# EEZ_PSU_AUX_PS_r5B9.net
KiCad netlist of a schematic drawn in EAGLE
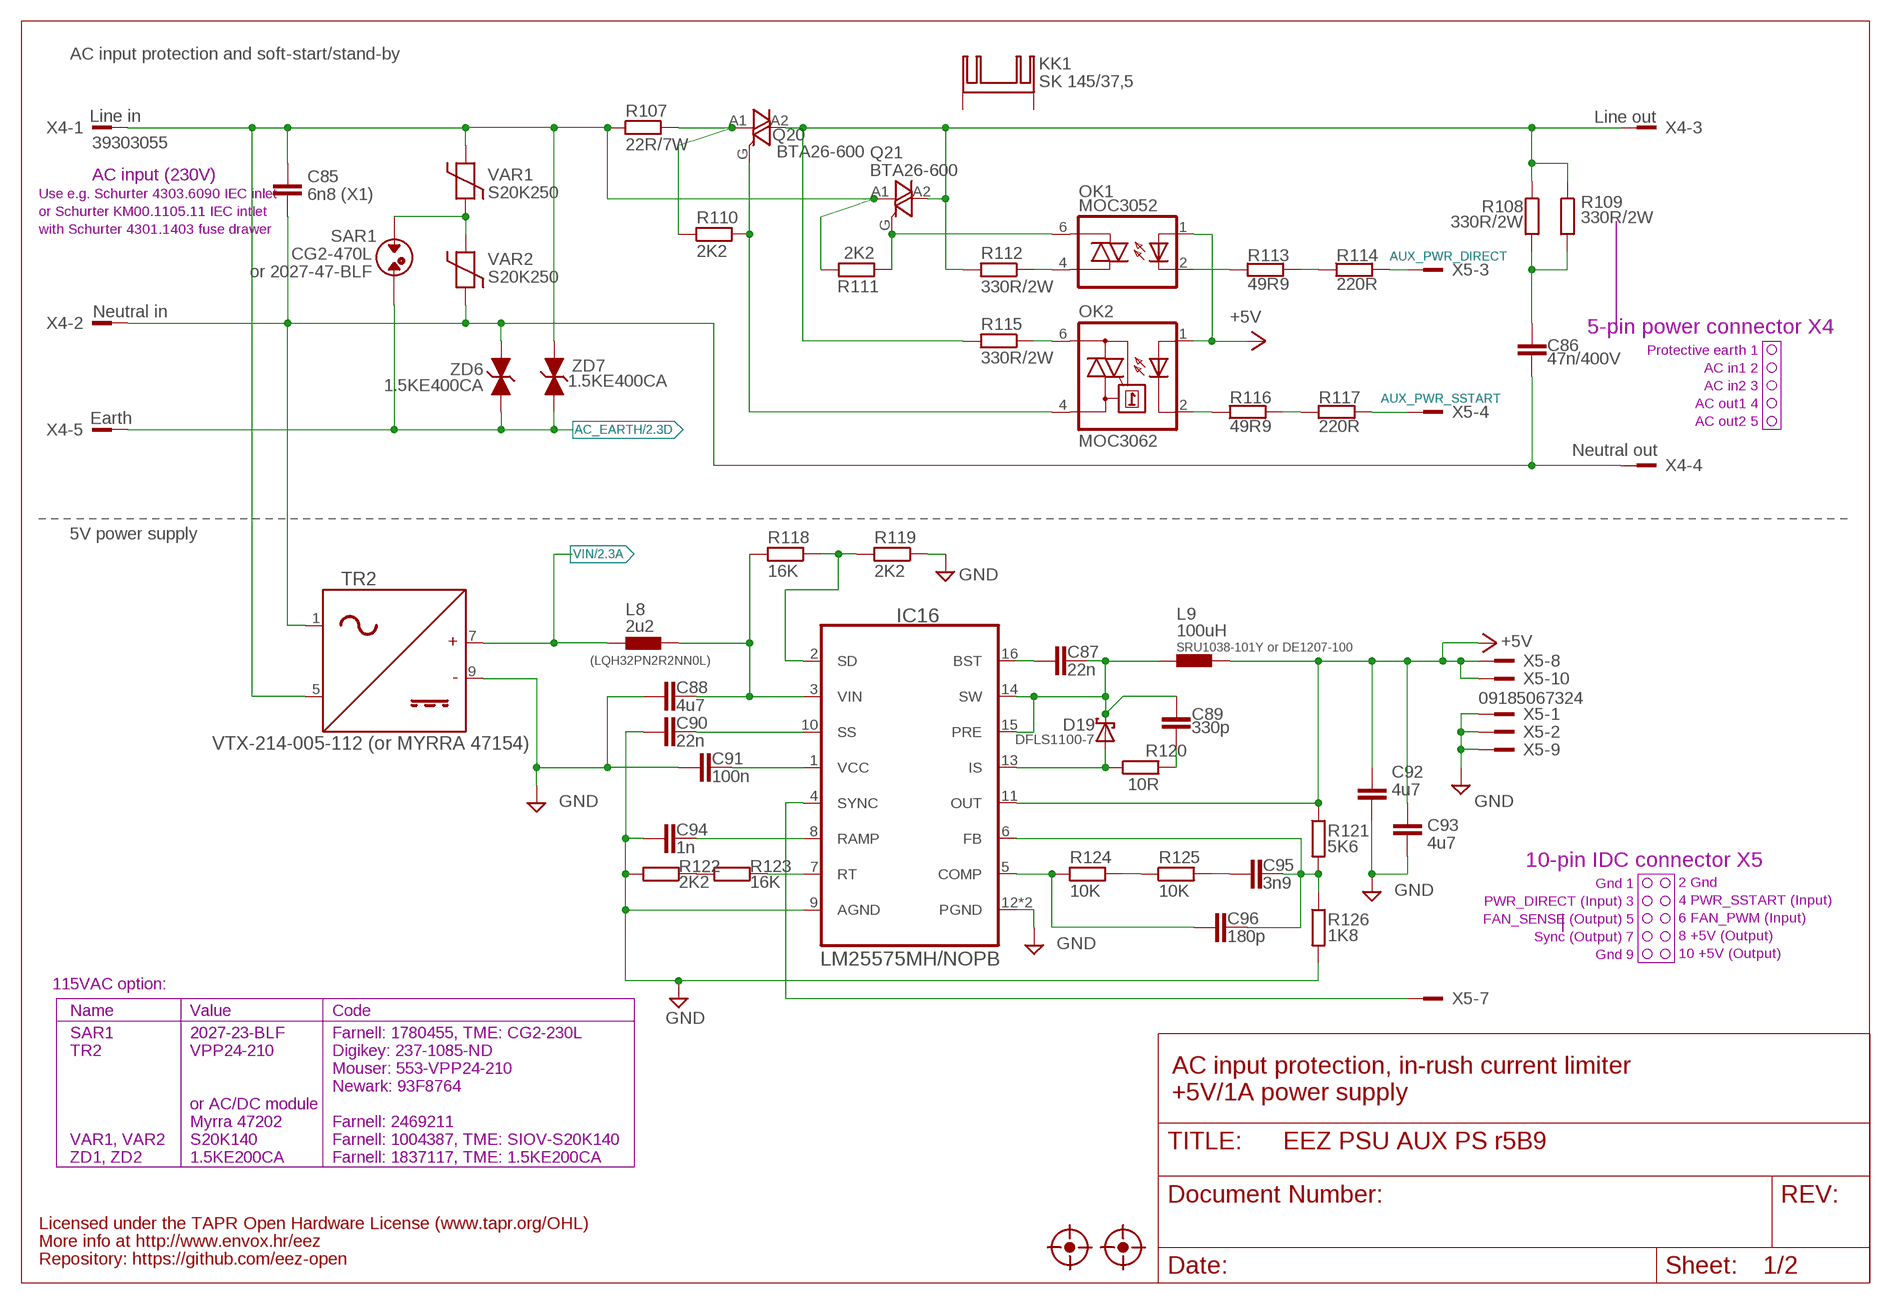
[diagram p0: schematic, sheet 1]
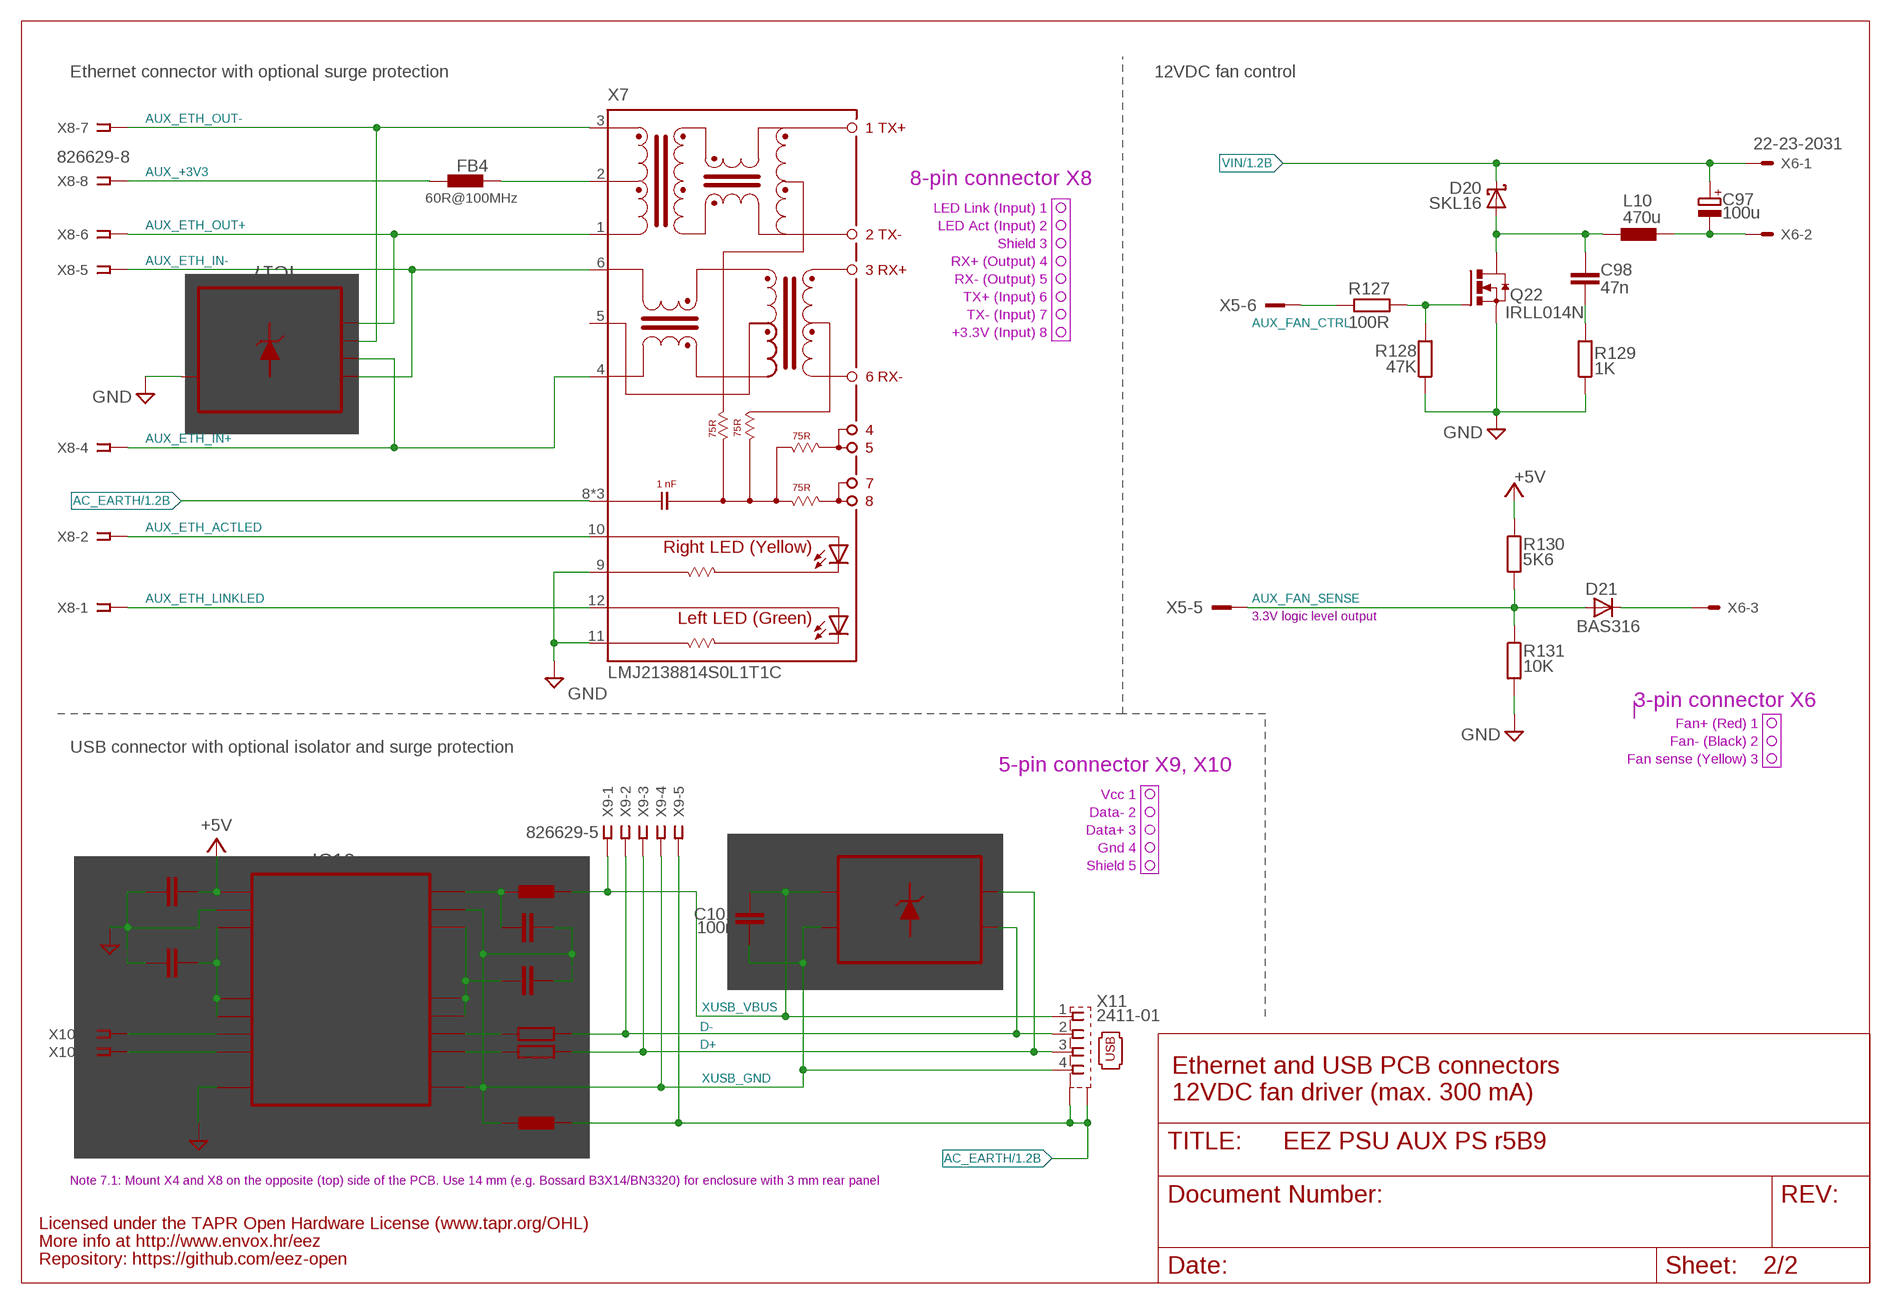
[diagram p1: schematic, sheet 2]

(export (version "E")
  (design (tool "Eeschema 10.0.6"))
  (components
    (comp (ref "C85")
      (value "6n8 (X1)")
      (footprint "eagle-import:C102-064X133")
      (libsource (lib "eagle-import") (part "C-EU102-064X133"))
    )
    (comp (ref "C86")
      (value "47n/400V")
      (footprint "eagle-import:C075-052X106")
      (libsource (lib "eagle-import") (part "C-EU075-052X106"))
    )
    (comp (ref "C87")
      (value "22n")
      (footprint "eagle-import:C0805")
      (libsource (lib "eagle-import") (part "C-EUC0805"))
    )
    (comp (ref "C88")
      (value "4u7")
      (footprint "eagle-import:C1210")
      (libsource (lib "eagle-import") (part "C-EUC1210"))
    )
    (comp (ref "C89")
      (value "330p")
      (footprint "eagle-import:C0805")
      (libsource (lib "eagle-import") (part "C-EUC0805"))
    )
    (comp (ref "C90")
      (value "22n")
      (footprint "eagle-import:C0805")
      (libsource (lib "eagle-import") (part "C-EUC0805"))
    )
    (comp (ref "C91")
      (value "100n")
      (footprint "eagle-import:C0603")
      (libsource (lib "eagle-import") (part "C-EUC0603"))
    )
    (comp (ref "C92")
      (value "4u7")
      (footprint "eagle-import:C1210")
      (libsource (lib "eagle-import") (part "C-EUC1210"))
    )
    (comp (ref "C93")
      (value "4u7")
      (footprint "eagle-import:C1210")
      (libsource (lib "eagle-import") (part "C-EUC1210"))
    )
    (comp (ref "C94")
      (value "1n")
      (footprint "eagle-import:C0805")
      (libsource (lib "eagle-import") (part "C-EUC0805"))
    )
    (comp (ref "C95")
      (value "3n9")
      (footprint "eagle-import:C0805")
      (libsource (lib "eagle-import") (part "C-EUC0805"))
    )
    (comp (ref "C96")
      (value "180p")
      (footprint "eagle-import:C0805")
      (libsource (lib "eagle-import") (part "C-EUC0805"))
    )
    (comp (ref "D19")
      (value "DFLS1100-7")
      (footprint "eagle-import:SOD123")
      (libsource (lib "eagle-import") (part "SCHOTTKYSOD123"))
    )
    (comp (ref "FM3")
      (value "FIDUCIAL_2")
      (footprint "eagle-import:FIDUCIAL_DUAL")
      (libsource (lib "eagle-import") (part "FIDUCIAL_2"))
    )
    (comp (ref "FM4")
      (value "FIDUCIAL_2")
      (footprint "eagle-import:FIDUCIAL_DUAL")
      (libsource (lib "eagle-import") (part "FIDUCIAL_2"))
    )
    (comp (ref "IC16")
      (value "LM25575MH/NOPB")
      (footprint "eagle-import:SOP65P640X110-17N")
      (libsource (lib "eagle-import") (part "LM(2)5575"))
    )
    (comp (ref "KK1")
      (value "SK 145/37,5")
      (footprint "eagle-import:SK145")
      (libsource (lib "eagle-import") (part "SK145"))
    )
    (comp (ref "L8")
      (value "2u2")
      (footprint "eagle-import:L1210")
      (libsource (lib "eagle-import") (part "L1210"))
    )
    (comp (ref "L9")
      (value "100uH")
      (footprint "eagle-import:MSS1278")
      (libsource (lib "eagle-import") (part "COILCRAFT_MSS1278"))
    )
    (comp (ref "OK1")
      (value "MOC3052")
      (footprint "eagle-import:DIL6-SMD")
      (libsource (lib "eagle-import") (part "MOC305X"))
    )
    (comp (ref "OK2")
      (value "MOC3062")
      (footprint "eagle-import:DIL6-SMD")
      (fields
        (field (name "MF") "FAIRCHILD SEMICONDUCTOR")
        (field (name "MPN") "MOC3033S-M")
        (field (name "MF_1") "FAIRCHILD SEMICONDUCTOR")
        (field (name "MPN_1") "MOC3033S-M")
        (field (name "OC_FARNELL") "unknown")
        (field (name "OC_NEWARK") "05C2878")
      )
      (libsource (lib "eagle-import") (part "MOC30S33"))
    )
    (comp (ref "Q20")
      (value "BTA26-600")
      (footprint "eagle-import:TOP3S-1")
      (libsource (lib "eagle-import") (part "BTA26-V"))
    )
    (comp (ref "Q21")
      (value "BTA26-600")
      (footprint "eagle-import:TOP3S-1")
      (libsource (lib "eagle-import") (part "BTA26-V"))
    )
    (comp (ref "R107")
      (value "22R/7W")
      (footprint "eagle-import:R_0913")
      (libsource (lib "eagle-import") (part "R_EU7W"))
    )
    (comp (ref "R108")
      (value "330R/2W")
      (footprint "eagle-import:R2512")
      (libsource (lib "eagle-import") (part "R-EU_R2512"))
    )
    (comp (ref "R109")
      (value "330R/2W")
      (footprint "eagle-import:R2512")
      (libsource (lib "eagle-import") (part "R-EU_R2512"))
    )
    (comp (ref "R110")
      (value "2K2")
      (footprint "eagle-import:R0805")
      (libsource (lib "eagle-import") (part "R-EU_R0805"))
    )
    (comp (ref "R111")
      (value "2K2")
      (footprint "eagle-import:R0805")
      (libsource (lib "eagle-import") (part "R-EU_R0805"))
    )
    (comp (ref "R112")
      (value "330R/2W")
      (footprint "eagle-import:R2512")
      (libsource (lib "eagle-import") (part "R-EU_R2512"))
    )
    (comp (ref "R113")
      (value "49R9")
      (footprint "eagle-import:R0805")
      (libsource (lib "eagle-import") (part "R-EU_R0805"))
    )
    (comp (ref "R114")
      (value "220R")
      (footprint "eagle-import:R0805")
      (libsource (lib "eagle-import") (part "R-EU_R0805"))
    )
    (comp (ref "R115")
      (value "330R/2W")
      (footprint "eagle-import:R2512")
      (libsource (lib "eagle-import") (part "R-EU_R2512"))
    )
    (comp (ref "R116")
      (value "49R9")
      (footprint "eagle-import:R0805")
      (libsource (lib "eagle-import") (part "R-EU_R0805"))
    )
    (comp (ref "R117")
      (value "220R")
      (footprint "eagle-import:R0805")
      (libsource (lib "eagle-import") (part "R-EU_R0805"))
    )
    (comp (ref "R118")
      (value "16K")
      (footprint "eagle-import:R0805")
      (libsource (lib "eagle-import") (part "R-EU_R0805"))
    )
    (comp (ref "R119")
      (value "2K2")
      (footprint "eagle-import:R0805")
      (libsource (lib "eagle-import") (part "R-EU_R0805"))
    )
    (comp (ref "R120")
      (value "10R")
      (footprint "eagle-import:R1206")
      (libsource (lib "eagle-import") (part "R-EU_R1206"))
    )
    (comp (ref "R121")
      (value "5K6")
      (footprint "eagle-import:R0805")
      (libsource (lib "eagle-import") (part "R-EU_R0805"))
    )
    (comp (ref "R122")
      (value "2K2")
      (footprint "eagle-import:R0805")
      (libsource (lib "eagle-import") (part "R-EU_R0805"))
    )
    (comp (ref "R123")
      (value "16K")
      (footprint "eagle-import:R0805")
      (libsource (lib "eagle-import") (part "R-EU_R0805"))
    )
    (comp (ref "R124")
      (value "10K")
      (footprint "eagle-import:R0805")
      (libsource (lib "eagle-import") (part "R-EU_R0805"))
    )
    (comp (ref "R125")
      (value "10K")
      (footprint "eagle-import:R0805")
      (libsource (lib "eagle-import") (part "R-EU_R0805"))
    )
    (comp (ref "R126")
      (value "1K8")
      (footprint "eagle-import:R0805")
      (libsource (lib "eagle-import") (part "R-EU_R0805"))
    )
    (comp (ref "SAR1")
      (value "CG2-470L")
      (footprint "eagle-import:SAR")
      (libsource (lib "eagle-import") (part "SAR"))
    )
    (comp (ref "TR2")
      (value "VTX-214-005-112 (or MYRRA 47154)")
      (footprint "eagle-import:PCB_ACDC_MYRRA_5W")
      (libsource (lib "eagle-import") (part "AC_DC_ADAPTER_5W"))
    )
    (comp (ref "VAR1")
      (value "S20K250")
      (footprint "eagle-import:VARISTOR")
      (libsource (lib "eagle-import") (part "VARISTOR"))
    )
    (comp (ref "VAR2")
      (value "S20K250")
      (footprint "eagle-import:VARISTOR")
      (libsource (lib "eagle-import") (part "VARISTOR"))
    )
    (comp (ref "X4")
      (value "39303055")
      (footprint "eagle-import:MINIFIT_6659-5")
      (libsource (lib "eagle-import") (part "MINIFIT_6659-5"))
    )
    (comp (ref "X5")
      (value "09185067324")
      (footprint "eagle-import:IDC-10PIN")
      (fields (field (name "TME") "T821-1-10-S1 "))
      (libsource (lib "eagle-import") (part "IDC-10PINBLACK"))
    )
    (comp (ref "ZD6")
      (value "1.5KE400CA")
      (footprint "eagle-import:DO201-BIDIR")
      (libsource (lib "eagle-import") (part "1.5KE-BIDIR"))
    )
    (comp (ref "ZD7")
      (value "1.5KE400CA")
      (footprint "eagle-import:DO201-BIDIR")
      (libsource (lib "eagle-import") (part "1.5KE-BIDIR"))
    )
    (comp (ref "C97")
      (value "100u")
      (footprint "eagle-import:CAPAE660X610N")
      (libsource (lib "eagle-import") (part "ECAPPANASONIC_H"))
    )
    (comp (ref "C98")
      (value "47n")
      (footprint "eagle-import:C0805")
      (libsource (lib "eagle-import") (part "C-EUC0805"))
    )
    (comp (ref "C99")
      (value "100n")
      (footprint "eagle-import:C0603")
      (libsource (lib "eagle-import") (part "C-EUC0603"))
    )
    (comp (ref "C100")
      (value "100n")
      (footprint "eagle-import:C0603")
      (libsource (lib "eagle-import") (part "C-EUC0603"))
    )
    (comp (ref "C101")
      (value "100n")
      (footprint "eagle-import:C0603")
      (libsource (lib "eagle-import") (part "C-EUC0603"))
    )
    (comp (ref "C102")
      (value "100n")
      (footprint "eagle-import:C0603")
      (libsource (lib "eagle-import") (part "C-EUC0603"))
    )
    (comp (ref "C103")
      (value "100n")
      (footprint "eagle-import:C0603")
      (libsource (lib "eagle-import") (part "C-EUC0603"))
    )
    (comp (ref "D20")
      (value "SKL16")
      (footprint "eagle-import:SOD123")
      (libsource (lib "eagle-import") (part "SCHOTTKYSOD123"))
    )
    (comp (ref "D21")
      (value "BAS316")
      (footprint "eagle-import:SOD323-W")
      (libsource (lib "eagle-import") (part "DIODE-SOD323-W"))
    )
    (comp (ref "FB4")
      (value "60R@100MHz")
      (footprint "eagle-import:BEAD0603")
      (libsource (lib "eagle-import") (part "FERRITE_BEAD0603"))
    )
    (comp (ref "FB5")
      (value "60R@100MHz")
      (footprint "eagle-import:BEAD0603")
      (libsource (lib "eagle-import") (part "FERRITE_BEAD0603"))
    )
    (comp (ref "FB6")
      (value "60R@100MHz")
      (footprint "eagle-import:BEAD0603")
      (libsource (lib "eagle-import") (part "FERRITE_BEAD0603"))
    )
    (comp (ref "IC17")
      (value "TPD4E002DRLR")
      (footprint "eagle-import:SOT50P280X60-5N")
      (libsource (lib "eagle-import") (part "TPD4E002DRLR"))
    )
    (comp (ref "IC18")
      (value "TPD2E001DZDR")
      (footprint "eagle-import:SOP192P292X122-4N")
      (libsource (lib "eagle-import") (part "TPD2E001DZDR"))
    )
    (comp (ref "IC19")
      (value "ADUM3160BRWZ")
      (footprint "eagle-import:SOIC-16W")
      (libsource (lib "eagle-import") (part "ADUM3160BRWZWIDE"))
    )
    (comp (ref "L10")
      (value "470u")
      (footprint "eagle-import:DE0704")
      (libsource (lib "eagle-import") (part "DE0704"))
    )
    (comp (ref "Q22")
      (value "IRLL014N")
      (footprint "eagle-import:SOT223")
      (libsource (lib "eagle-import") (part "N-HEXFET-2D_?-SOT232IRLL014N"))
    )
    (comp (ref "R127")
      (value "100R")
      (footprint "eagle-import:R0805")
      (libsource (lib "eagle-import") (part "R-EU_R0805"))
    )
    (comp (ref "R128")
      (value "47K")
      (footprint "eagle-import:R0805")
      (libsource (lib "eagle-import") (part "R-EU_R0805"))
    )
    (comp (ref "R129")
      (value "1K")
      (footprint "eagle-import:R0805")
      (libsource (lib "eagle-import") (part "R-EU_R0805"))
    )
    (comp (ref "R130")
      (value "5K6")
      (footprint "eagle-import:R0805")
      (libsource (lib "eagle-import") (part "R-EU_R0805"))
    )
    (comp (ref "R131")
      (value "10K")
      (footprint "eagle-import:R0805")
      (libsource (lib "eagle-import") (part "R-EU_R0805"))
    )
    (comp (ref "R132")
      (value "22R")
      (footprint "eagle-import:R0805")
      (libsource (lib "eagle-import") (part "R-EU_R0805"))
    )
    (comp (ref "R133")
      (value "22R")
      (footprint "eagle-import:R0805")
      (libsource (lib "eagle-import") (part "R-EU_R0805"))
    )
    (comp (ref "X6")
      (value "22-23-2031")
      (footprint "eagle-import:22-23-2031")
      (fields (field (name "MF") "MOLEX"))
      (libsource (lib "eagle-import") (part "22-23-2031"))
    )
    (comp (ref "X7")
      (value "LMJ2138814S0L1T1C")
      (footprint "eagle-import:RJ45-VERT")
      (libsource (lib "eagle-import") (part "RJ45-VERTLMJ2138814S0L1T1C"))
    )
    (comp (ref "X8")
      (value "826629-8")
      (footprint "eagle-import:SSW-108-02-S-S")
      (fields (field (name "MPN") "SSW-108-02-S-S"))
      (libsource (lib "eagle-import") (part "SSW-108-02-S-S"))
    )
    (comp (ref "X9")
      (value "826629-5")
      (footprint "eagle-import:SSW-105-02-S-S")
      (fields (field (name "MPN") "SSW-105-02-S-S"))
      (libsource (lib "eagle-import") (part "SSW-105-02-S-S"))
    )
    (comp (ref "X10")
      (value "826629-5")
      (footprint "eagle-import:SSW-105-02-S-S")
      (fields (field (name "MPN") "SSW-105-02-S-S"))
      (libsource (lib "eagle-import") (part "SSW-105-02-S-S"))
    )
    (comp (ref "X11")
      (value "2411-01")
      (footprint "eagle-import:KUSBVX-BS1N")
      (libsource (lib "eagle-import") (part "KUSBVX-BS1N"))
    )
  )
  (nets
    (net (code "1") (name "+5V") (class "Default")
      (node (ref "C92") (pin "1") (pinfunction "1_1") (pintype "passive"))
      (node (ref "C93") (pin "1") (pinfunction "1_1") (pintype "passive"))
      (node (ref "C99") (pin "1") (pinfunction "1_1") (pintype "passive"))
      (node (ref "IC16") (pin "11") (pinfunction "OUT_11") (pintype "output"))
      (node (ref "IC19") (pin "16") (pinfunction "VBUS2_16") (pintype "power_in"))
      (node (ref "L9") (pin "2") (pinfunction "2_2") (pintype "passive"))
      (node (ref "OK1") (pin "1") (pinfunction "A_1") (pintype "passive"))
      (node (ref "OK2") (pin "1") (pinfunction "A_1") (pintype "passive"))
      (node (ref "R121") (pin "1") (pinfunction "1_1") (pintype "passive"))
      (node (ref "R130") (pin "1") (pinfunction "1_1") (pintype "passive"))
      (node (ref "X5") (pin "10") (pinfunction "1_10") (pintype "passive"))
      (node (ref "X5") (pin "8") (pinfunction "1_8") (pintype "passive"))
    )
    (net (code "2") (name "AC_EARTH") (class "Default")
      (node (ref "FB6") (pin "P$1") (pinfunction "1_P$1") (pintype "passive"))
      (node (ref "SAR1") (pin "P$2") (pinfunction "P$2_P$2") (pintype "bidirectional"))
      (node (ref "X11") (pin "M1") (pinfunction "S1_M1") (pintype "passive"))
      (node (ref "X11") (pin "M2") (pinfunction "S2_M2") (pintype "passive"))
      (node (ref "X4") (pin "5") (pinfunction "1_5") (pintype "passive"))
      (node (ref "X7") (pin "8") (pinfunction "SH_8") (pintype "input"))
      (node (ref "X7") (pin "SH1") (pinfunction "SH_SH1") (pintype "input"))
      (node (ref "X7") (pin "SH2") (pinfunction "SH_SH2") (pintype "input"))
      (node (ref "X9") (pin "5") (pinfunction "1_5") (pintype "passive"))
      (node (ref "ZD6") (pin "C") (pinfunction "1_C") (pintype "passive"))
      (node (ref "ZD7") (pin "C") (pinfunction "1_C") (pintype "passive"))
    )
    (net (code "3") (name "AUX_+3V3") (class "Default")
      (node (ref "FB4") (pin "P$2") (pinfunction "2_P$2") (pintype "passive"))
      (node (ref "X8") (pin "8") (pinfunction "1_8") (pintype "passive"))
    )
    (net (code "4") (name "AUX_ETH_ACTLED") (class "Default")
      (node (ref "X7") (pin "10") (pinfunction "YELLOW_A_10") (pintype "passive"))
      (node (ref "X8") (pin "2") (pinfunction "1_2") (pintype "passive"))
    )
    (net (code "5") (name "AUX_ETH_IN+") (class "Default")
      (node (ref "IC17") (pin "4") (pinfunction "IO3_4") (pintype "bidirectional"))
      (node (ref "X7") (pin "4") (pinfunction "RD-_4") (pintype "input"))
      (node (ref "X8") (pin "4") (pinfunction "1_4") (pintype "passive"))
    )
    (net (code "6") (name "AUX_ETH_IN-") (class "Default")
      (node (ref "IC17") (pin "5") (pinfunction "IO4_5") (pintype "bidirectional"))
      (node (ref "X7") (pin "6") (pinfunction "RD+_6") (pintype "input"))
      (node (ref "X8") (pin "5") (pinfunction "1_5") (pintype "passive"))
    )
    (net (code "7") (name "AUX_ETH_LINKLED") (class "Default")
      (node (ref "X7") (pin "12") (pinfunction "GREEN-A_12") (pintype "passive"))
      (node (ref "X8") (pin "1") (pinfunction "1_1") (pintype "passive"))
    )
    (net (code "8") (name "AUX_ETH_OUT+") (class "Default")
      (node (ref "IC17") (pin "1") (pinfunction "IO1_1") (pintype "bidirectional"))
      (node (ref "X7") (pin "1") (pinfunction "TD-_1") (pintype "input"))
      (node (ref "X8") (pin "6") (pinfunction "1_6") (pintype "passive"))
    )
    (net (code "9") (name "AUX_ETH_OUT-") (class "Default")
      (node (ref "IC17") (pin "3") (pinfunction "IO2_3") (pintype "bidirectional"))
      (node (ref "X7") (pin "3") (pinfunction "TD+_3") (pintype "input"))
      (node (ref "X8") (pin "7") (pinfunction "1_7") (pintype "passive"))
    )
    (net (code "10") (name "AUX_FAN_CTRL") (class "Default")
      (node (ref "R127") (pin "2") (pinfunction "2_2") (pintype "passive"))
      (node (ref "X5") (pin "6") (pinfunction "1_6") (pintype "passive"))
    )
    (net (code "11") (name "AUX_FAN_SENSE") (class "Default")
      (node (ref "D21") (pin "A") (pinfunction "A_A") (pintype "passive"))
      (node (ref "R130") (pin "2") (pinfunction "2_2") (pintype "passive"))
      (node (ref "R131") (pin "1") (pinfunction "1_1") (pintype "passive"))
      (node (ref "X5") (pin "5") (pinfunction "1_5") (pintype "passive"))
    )
    (net (code "12") (name "AUX_PWR_DIRECT") (class "Default")
      (node (ref "R114") (pin "2") (pinfunction "2_2") (pintype "passive"))
      (node (ref "X5") (pin "3") (pinfunction "1_3") (pintype "passive"))
    )
    (net (code "13") (name "AUX_PWR_SSTART") (class "Default")
      (node (ref "R117") (pin "2") (pinfunction "2_2") (pintype "passive"))
      (node (ref "X5") (pin "4") (pinfunction "1_4") (pintype "passive"))
    )
    (net (code "14") (name "D+") (class "Default")
      (node (ref "IC18") (pin "2") (pinfunction "IO1_2") (pintype "bidirectional"))
      (node (ref "R133") (pin "1") (pinfunction "1_1") (pintype "passive"))
      (node (ref "X11") (pin "3") (pinfunction "3_3") (pintype "passive"))
      (node (ref "X9") (pin "3") (pinfunction "1_3") (pintype "passive"))
    )
    (net (code "15") (name "D-") (class "Default")
      (node (ref "IC18") (pin "3") (pinfunction "IO2_3") (pintype "bidirectional"))
      (node (ref "R132") (pin "1") (pinfunction "1_1") (pintype "passive"))
      (node (ref "X11") (pin "2") (pinfunction "2_2") (pintype "passive"))
      (node (ref "X9") (pin "2") (pinfunction "1_2") (pintype "passive"))
    )
    (net (code "16") (name "GND") (class "Default")
      (node (ref "C102") (pin "2") (pinfunction "2_2") (pintype "passive"))
      (node (ref "C88") (pin "2") (pinfunction "2_2") (pintype "passive"))
      (node (ref "C90") (pin "2") (pinfunction "2_2") (pintype "passive"))
      (node (ref "C91") (pin "1") (pinfunction "1_1") (pintype "passive"))
      (node (ref "C92") (pin "2") (pinfunction "2_2") (pintype "passive"))
      (node (ref "C93") (pin "2") (pinfunction "2_2") (pintype "passive"))
      (node (ref "C94") (pin "1") (pinfunction "1_1") (pintype "passive"))
      (node (ref "C99") (pin "2") (pinfunction "2_2") (pintype "passive"))
      (node (ref "IC16") (pin "12") (pinfunction "PGND_12") (pintype "passive"))
      (node (ref "IC16") (pin "9") (pinfunction "AGND_9") (pintype "passive"))
      (node (ref "IC16") (pin "TP") (pinfunction "PGND_TP") (pintype "passive"))
      (node (ref "IC17") (pin "2") (pinfunction "GND_2") (pintype "passive"))
      (node (ref "IC19") (pin "15") (pinfunction "GND2_2_15") (pintype "passive"))
      (node (ref "IC19") (pin "9") (pinfunction "GND2_9") (pintype "passive"))
      (node (ref "Q22") (pin "3") (pinfunction "S_3") (pintype "passive"))
      (node (ref "R119") (pin "1") (pinfunction "1_1") (pintype "passive"))
      (node (ref "R122") (pin "2") (pinfunction "2_2") (pintype "passive"))
      (node (ref "R126") (pin "2") (pinfunction "2_2") (pintype "passive"))
      (node (ref "R128") (pin "1") (pinfunction "1_1") (pintype "passive"))
      (node (ref "R129") (pin "1") (pinfunction "1_1") (pintype "passive"))
      (node (ref "R131") (pin "2") (pinfunction "2_2") (pintype "passive"))
      (node (ref "TR2") (pin "9") (pinfunction "-_9") (pintype "passive"))
      (node (ref "X5") (pin "1") (pinfunction "1_1") (pintype "passive"))
      (node (ref "X5") (pin "2") (pinfunction "1_2") (pintype "passive"))
      (node (ref "X5") (pin "9") (pinfunction "1_9") (pintype "passive"))
      (node (ref "X7") (pin "11") (pinfunction "GREEN-C_11") (pintype "passive"))
      (node (ref "X7") (pin "9") (pinfunction "YELLOW-C_9") (pintype "passive"))
    )
    (net (code "17") (name "Net-(C86-Pad2)") (class "Default")
      (node (ref "C86") (pin "2") (pinfunction "2_2") (pintype "passive"))
      (node (ref "R108") (pin "2") (pinfunction "2_2") (pintype "passive"))
      (node (ref "R109") (pin "2") (pinfunction "2_2") (pintype "passive"))
    )
    (net (code "18") (name "Net-(C89-Pad2)") (class "Default")
      (node (ref "C89") (pin "2") (pinfunction "2_2") (pintype "passive"))
      (node (ref "R120") (pin "2") (pinfunction "2_2") (pintype "passive"))
    )
    (net (code "19") (name "Net-(C95-Pad2)") (class "Default")
      (node (ref "C95") (pin "2") (pinfunction "2_2") (pintype "passive"))
      (node (ref "R125") (pin "2") (pinfunction "2_2") (pintype "passive"))
    )
    (net (code "20") (name "Net-(C97--)") (class "Default")
      (node (ref "C97") (pin "2") (pinfunction "-_2") (pintype "passive"))
      (node (ref "L10") (pin "1") (pinfunction "1_1") (pintype "passive"))
      (node (ref "X6") (pin "2") (pinfunction "S_2") (pintype "passive"))
    )
    (net (code "21") (name "Net-(C98-Pad1)") (class "Default")
      (node (ref "C98") (pin "1") (pinfunction "1_1") (pintype "passive"))
      (node (ref "R129") (pin "2") (pinfunction "2_2") (pintype "passive"))
    )
    (net (code "22") (name "Net-(C98-Pad2)") (class "Default")
      (node (ref "C98") (pin "2") (pinfunction "2_2") (pintype "passive"))
      (node (ref "D20") (pin "A") (pinfunction "A_A") (pintype "passive"))
      (node (ref "L10") (pin "2") (pinfunction "2_2") (pintype "passive"))
      (node (ref "Q22") (pin "2") (pinfunction "D_2") (pintype "passive"))
      (node (ref "Q22") (pin "4") (pinfunction "D_4") (pintype "passive"))
    )
    (net (code "23") (name "Net-(FB4-1)") (class "Default")
      (node (ref "FB4") (pin "P$1") (pinfunction "1_P$1") (pintype "passive"))
      (node (ref "X7") (pin "2") (pinfunction "CT_2") (pintype "input"))
    )
    (net (code "24") (name "Net-(FB5-2)") (class "Default")
      (node (ref "C100") (pin "1") (pinfunction "1_1") (pintype "passive"))
      (node (ref "FB5") (pin "P$2") (pinfunction "2_P$2") (pintype "passive"))
      (node (ref "IC19") (pin "1") (pinfunction "VBUS1_1") (pintype "power_in"))
    )
    (net (code "25") (name "Net-(IC16-BST)") (class "Default")
      (node (ref "C87") (pin "2") (pinfunction "2_2") (pintype "passive"))
      (node (ref "IC16") (pin "16") (pinfunction "BST_16") (pintype "input"))
    )
    (net (code "26") (name "Net-(IC16-COMP)") (class "Default")
      (node (ref "C96") (pin "2") (pinfunction "2_2") (pintype "passive"))
      (node (ref "IC16") (pin "5") (pinfunction "COMP_5") (pintype "input"))
      (node (ref "R124") (pin "1") (pinfunction "1_1") (pintype "passive"))
    )
    (net (code "27") (name "Net-(IC16-FB)") (class "Default")
      (node (ref "C95") (pin "1") (pinfunction "1_1") (pintype "passive"))
      (node (ref "C96") (pin "1") (pinfunction "1_1") (pintype "passive"))
      (node (ref "IC16") (pin "6") (pinfunction "FB_6") (pintype "input"))
      (node (ref "R121") (pin "2") (pinfunction "2_2") (pintype "passive"))
      (node (ref "R126") (pin "1") (pinfunction "1_1") (pintype "passive"))
    )
    (net (code "28") (name "Net-(IC16-IS)") (class "Default")
      (node (ref "D19") (pin "A") (pinfunction "A_A") (pintype "passive"))
      (node (ref "IC16") (pin "13") (pinfunction "IS_13") (pintype "input"))
      (node (ref "R120") (pin "1") (pinfunction "1_1") (pintype "passive"))
    )
    (net (code "29") (name "Net-(IC16-PRE)") (class "Default")
      (node (ref "C87") (pin "1") (pinfunction "1_1") (pintype "passive"))
      (node (ref "C89") (pin "1") (pinfunction "1_1") (pintype "passive"))
      (node (ref "D19") (pin "C") (pinfunction "C_C") (pintype "passive"))
      (node (ref "IC16") (pin "14") (pinfunction "SW_14") (pintype "output"))
      (node (ref "IC16") (pin "15") (pinfunction "PRE_15") (pintype "input"))
      (node (ref "L9") (pin "1") (pinfunction "1_1") (pintype "passive"))
    )
    (net (code "30") (name "Net-(IC16-RAMP)") (class "Default")
      (node (ref "C94") (pin "2") (pinfunction "2_2") (pintype "passive"))
      (node (ref "IC16") (pin "8") (pinfunction "RAMP_8") (pintype "input"))
    )
    (net (code "31") (name "Net-(IC16-RT)") (class "Default")
      (node (ref "IC16") (pin "7") (pinfunction "RT_7") (pintype "input"))
      (node (ref "R123") (pin "1") (pinfunction "1_1") (pintype "passive"))
    )
    (net (code "32") (name "Net-(IC16-SD)") (class "Default")
      (node (ref "IC16") (pin "2") (pinfunction "SD_2") (pintype "input"))
      (node (ref "R118") (pin "1") (pinfunction "1_1") (pintype "passive"))
      (node (ref "R119") (pin "2") (pinfunction "2_2") (pintype "passive"))
    )
    (net (code "33") (name "Net-(IC16-SS)") (class "Default")
      (node (ref "C90") (pin "1") (pinfunction "1_1") (pintype "passive"))
      (node (ref "IC16") (pin "10") (pinfunction "SS_10") (pintype "input"))
    )
    (net (code "34") (name "Net-(IC16-SYNC)") (class "Default")
      (node (ref "IC16") (pin "4") (pinfunction "SYNC_4") (pintype "input"))
      (node (ref "X5") (pin "7") (pinfunction "1_7") (pintype "passive"))
    )
    (net (code "35") (name "Net-(IC16-VCC)") (class "Default")
      (node (ref "C91") (pin "2") (pinfunction "2_2") (pintype "passive"))
      (node (ref "IC16") (pin "1") (pinfunction "VCC_1") (pintype "power_in"))
    )
    (net (code "36") (name "Net-(IC16-VIN)") (class "Default")
      (node (ref "C88") (pin "1") (pinfunction "1_1") (pintype "passive"))
      (node (ref "IC16") (pin "3") (pinfunction "VIN_3") (pintype "input"))
      (node (ref "L8") (pin "2") (pinfunction "2_2") (pintype "passive"))
      (node (ref "R118") (pin "2") (pinfunction "2_2") (pintype "passive"))
    )
    (net (code "37") (name "Net-(IC19-DD+)") (class "Default")
      (node (ref "IC19") (pin "10") (pinfunction "DD+_10") (pintype "bidirectional"))
      (node (ref "X10") (pin "3") (pinfunction "1_3") (pintype "passive"))
    )
    (net (code "38") (name "Net-(IC19-DD-)") (class "Default")
      (node (ref "IC19") (pin "11") (pinfunction "DD-_11") (pintype "bidirectional"))
      (node (ref "X10") (pin "2") (pinfunction "1_2") (pintype "passive"))
    )
    (net (code "39") (name "Net-(IC19-PDEN)") (class "Default")
      (node (ref "C103") (pin "1") (pinfunction "1_1") (pintype "passive"))
      (node (ref "IC19") (pin "3") (pinfunction "VDD1_3") (pintype "power_in"))
      (node (ref "IC19") (pin "4") (pinfunction "PDEN_4") (pintype "input"))
      (node (ref "IC19") (pin "5") (pinfunction "SPU_5") (pintype "input"))
    )
    (net (code "40") (name "Net-(IC19-PIN)") (class "Default")
      (node (ref "C102") (pin "1") (pinfunction "1_1") (pintype "passive"))
      (node (ref "IC19") (pin "12") (pinfunction "PIN_12") (pintype "input"))
      (node (ref "IC19") (pin "13") (pinfunction "SPD_13") (pintype "input"))
      (node (ref "IC19") (pin "14") (pinfunction "VDD2_14") (pintype "power_in"))
    )
    (net (code "41") (name "Net-(IC19-UD+)") (class "Default")
      (node (ref "IC19") (pin "7") (pinfunction "UD+_7") (pintype "bidirectional"))
      (node (ref "R133") (pin "2") (pinfunction "2_2") (pintype "passive"))
    )
    (net (code "42") (name "Net-(IC19-UD-)") (class "Default")
      (node (ref "IC19") (pin "6") (pinfunction "UD-_6") (pintype "bidirectional"))
      (node (ref "R132") (pin "2") (pinfunction "2_2") (pintype "passive"))
    )
    (net (code "43") (name "Net-(OK1-A1)") (class "Default")
      (node (ref "OK1") (pin "4") (pinfunction "A1_4") (pintype "passive"))
      (node (ref "R112") (pin "1") (pinfunction "1_1") (pintype "passive"))
    )
    (net (code "44") (name "Net-(OK1-A2)") (class "Default")
      (node (ref "OK1") (pin "6") (pinfunction "A2_6") (pintype "passive"))
      (node (ref "Q21") (pin "G") (pinfunction "G_G") (pintype "passive"))
      (node (ref "R111") (pin "1") (pinfunction "1_1") (pintype "passive"))
    )
    (net (code "45") (name "Net-(OK1-C)") (class "Default")
      (node (ref "OK1") (pin "2") (pinfunction "C_2") (pintype "passive"))
      (node (ref "R113") (pin "1") (pinfunction "1_1") (pintype "passive"))
    )
    (net (code "46") (name "Net-(OK2-A1)") (class "Default")
      (node (ref "OK2") (pin "4") (pinfunction "A1_4") (pintype "passive"))
      (node (ref "Q20") (pin "G") (pinfunction "G_G") (pintype "passive"))
      (node (ref "R110") (pin "2") (pinfunction "2_2") (pintype "passive"))
    )
    (net (code "47") (name "Net-(OK2-A2)") (class "Default")
      (node (ref "OK2") (pin "6") (pinfunction "A2_6") (pintype "passive"))
      (node (ref "R115") (pin "1") (pinfunction "1_1") (pintype "passive"))
    )
    (net (code "48") (name "Net-(OK2-C)") (class "Default")
      (node (ref "OK2") (pin "2") (pinfunction "C_2") (pintype "passive"))
      (node (ref "R116") (pin "1") (pinfunction "1_1") (pintype "passive"))
    )
    (net (code "49") (name "Net-(Q20-PadA1)") (class "Default")
      (node (ref "Q20") (pin "A1") (pinfunction "A1_A1") (pintype "passive"))
      (node (ref "R107") (pin "2") (pinfunction "2_2") (pintype "passive"))
      (node (ref "R110") (pin "1") (pinfunction "1_1") (pintype "passive"))
    )
    (net (code "50") (name "Net-(Q22-G)") (class "Default")
      (node (ref "Q22") (pin "1") (pinfunction "G_1") (pintype "passive"))
      (node (ref "R127") (pin "1") (pinfunction "1_1") (pintype "passive"))
      (node (ref "R128") (pin "2") (pinfunction "2_2") (pintype "passive"))
    )
    (net (code "51") (name "Net-(R113-Pad2)") (class "Default")
      (node (ref "R113") (pin "2") (pinfunction "2_2") (pintype "passive"))
      (node (ref "R114") (pin "1") (pinfunction "1_1") (pintype "passive"))
    )
    (net (code "52") (name "Net-(R116-Pad2)") (class "Default")
      (node (ref "R116") (pin "2") (pinfunction "2_2") (pintype "passive"))
      (node (ref "R117") (pin "1") (pinfunction "1_1") (pintype "passive"))
    )
    (net (code "53") (name "Net-(R122-Pad1)") (class "Default")
      (node (ref "R122") (pin "1") (pinfunction "1_1") (pintype "passive"))
      (node (ref "R123") (pin "2") (pinfunction "2_2") (pintype "passive"))
    )
    (net (code "54") (name "Net-(R124-Pad2)") (class "Default")
      (node (ref "R124") (pin "2") (pinfunction "2_2") (pintype "passive"))
      (node (ref "R125") (pin "1") (pinfunction "1_1") (pintype "passive"))
    )
    (net (code "55") (name "Net-(SAR1-PadP$1)") (class "Default")
      (node (ref "SAR1") (pin "P$1") (pinfunction "P$1_P$1") (pintype "bidirectional"))
      (node (ref "VAR1") (pin "P$1") (pinfunction "P$1_P$1") (pintype "bidirectional"))
      (node (ref "VAR2") (pin "P$2") (pinfunction "P$2_P$2") (pintype "bidirectional"))
    )
    (net (code "56") (name "Net-(TR2-IN1)") (class "Default")
      (node (ref "C85") (pin "2") (pinfunction "2_2") (pintype "passive"))
      (node (ref "C86") (pin "1") (pinfunction "1_1") (pintype "passive"))
      (node (ref "TR2") (pin "1") (pinfunction "IN1_1") (pintype "input"))
      (node (ref "VAR2") (pin "P$1") (pinfunction "P$1_P$1") (pintype "bidirectional"))
      (node (ref "X4") (pin "2") (pinfunction "1_2") (pintype "passive"))
      (node (ref "X4") (pin "4") (pinfunction "1_4") (pintype "passive"))
      (node (ref "ZD6") (pin "A") (pinfunction "2_A") (pintype "passive"))
    )
    (net (code "57") (name "Net-(TR2-IN2)") (class "Default")
      (node (ref "C85") (pin "1") (pinfunction "1_1") (pintype "passive"))
      (node (ref "Q21") (pin "A1") (pinfunction "A1_A1") (pintype "passive"))
      (node (ref "R107") (pin "1") (pinfunction "1_1") (pintype "passive"))
      (node (ref "R111") (pin "2") (pinfunction "2_2") (pintype "passive"))
      (node (ref "TR2") (pin "5") (pinfunction "IN2_5") (pintype "input"))
      (node (ref "VAR1") (pin "P$2") (pinfunction "P$2_P$2") (pintype "bidirectional"))
      (node (ref "X4") (pin "1") (pinfunction "1_1") (pintype "passive"))
      (node (ref "ZD7") (pin "A") (pinfunction "2_A") (pintype "passive"))
    )
    (net (code "58") (name "Net-(X4C-1)") (class "Default")
      (node (ref "Q20") (pin "A2") (pinfunction "A2_A2") (pintype "passive"))
      (node (ref "Q21") (pin "A2") (pinfunction "A2_A2") (pintype "passive"))
      (node (ref "R108") (pin "1") (pinfunction "1_1") (pintype "passive"))
      (node (ref "R109") (pin "1") (pinfunction "1_1") (pintype "passive"))
      (node (ref "R112") (pin "2") (pinfunction "2_2") (pintype "passive"))
      (node (ref "R115") (pin "2") (pinfunction "2_2") (pintype "passive"))
      (node (ref "X4") (pin "3") (pinfunction "1_3") (pintype "passive"))
    )
    (net (code "59") (name "Net-(X6C-S)") (class "Default")
      (node (ref "D21") (pin "C") (pinfunction "C_C") (pintype "passive"))
      (node (ref "X6") (pin "3") (pinfunction "S_3") (pintype "passive"))
    )
    (net (code "60") (name "VIN") (class "Default")
      (node (ref "C97") (pin "1") (pinfunction "+_1") (pintype "passive"))
      (node (ref "D20") (pin "C") (pinfunction "C_C") (pintype "passive"))
      (node (ref "L8") (pin "1") (pinfunction "1_1") (pintype "passive"))
      (node (ref "TR2") (pin "7") (pinfunction "+_7") (pintype "passive"))
      (node (ref "X6") (pin "1") (pinfunction "S_1") (pintype "passive"))
    )
    (net (code "61") (name "XUSB_GND") (class "Default")
      (node (ref "C100") (pin "2") (pinfunction "2_2") (pintype "passive"))
      (node (ref "C101") (pin "1") (pinfunction "1_1") (pintype "passive"))
      (node (ref "C103") (pin "2") (pinfunction "2_2") (pintype "passive"))
      (node (ref "FB6") (pin "P$2") (pinfunction "2_P$2") (pintype "passive"))
      (node (ref "IC18") (pin "1") (pinfunction "GND_1") (pintype "passive"))
      (node (ref "IC19") (pin "2") (pinfunction "GND1_2_2") (pintype "passive"))
      (node (ref "IC19") (pin "8") (pinfunction "GND1_8") (pintype "passive"))
      (node (ref "X11") (pin "4") (pinfunction "4_4") (pintype "passive"))
      (node (ref "X9") (pin "4") (pinfunction "1_4") (pintype "passive"))
    )
    (net (code "62") (name "XUSB_VBUS") (class "Default")
      (node (ref "C101") (pin "2") (pinfunction "2_2") (pintype "passive"))
      (node (ref "FB5") (pin "P$1") (pinfunction "1_P$1") (pintype "passive"))
      (node (ref "IC18") (pin "4") (pinfunction "VCC_4") (pintype "power_in"))
      (node (ref "X11") (pin "1") (pinfunction "1_1") (pintype "passive"))
      (node (ref "X9") (pin "1") (pinfunction "1_1") (pintype "passive"))
    )
    (net (code "63") (name "unconnected-(KK1-K-Pad1)") (class "Default")
      (node (ref "KK1") (pin "1") (pinfunction "K_1") (pintype "no_connect"))
    )
    (net (code "64") (name "unconnected-(KK1-K-Pad2)") (class "Default")
      (node (ref "KK1") (pin "2") (pinfunction "K_2") (pintype "no_connect"))
    )
    (net (code "65") (name "unconnected-(X7-CR-Pad5)") (class "Default")
      (node (ref "X7") (pin "5") (pinfunction "CR_5") (pintype "input"))
    )
  )
)
